# cp2102n-uart-usb.net
KiCad netlist of a schematic drawn in EAGLE
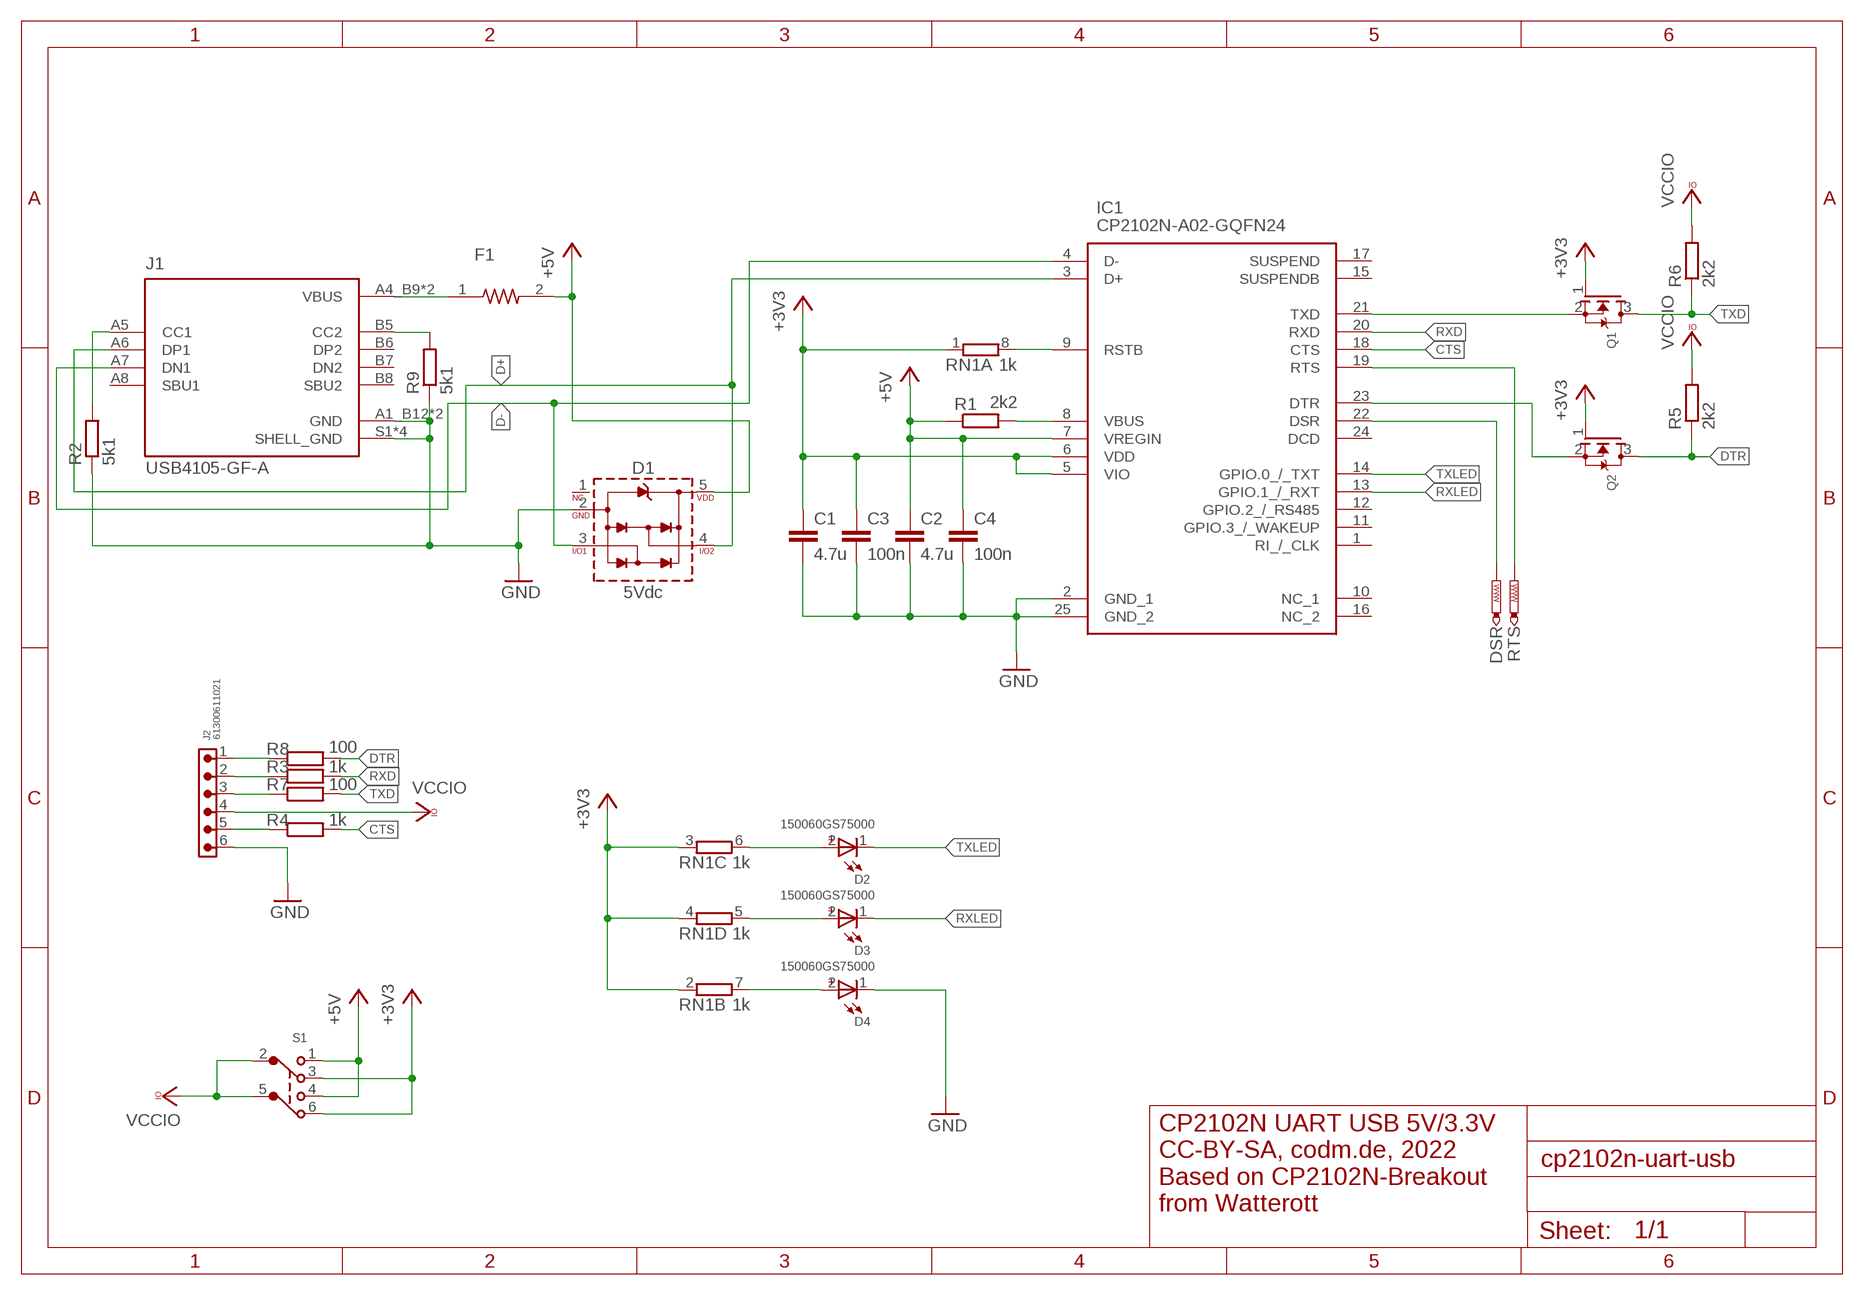
[diagram p0: schematic, sheet 1]

(export (version "E")
  (design (tool "Eeschema 10.0.6"))
  (components
    (comp (ref "C1")
      (value "4.7u")
      (footprint "eagle-import:C0603K")
      (libsource (lib "eagle-import") (part "C-EUC0603K"))
    )
    (comp (ref "C2")
      (value "4.7u")
      (footprint "eagle-import:C0603K")
      (libsource (lib "eagle-import") (part "C-EUC0603K"))
    )
    (comp (ref "C3")
      (value "100n")
      (footprint "eagle-import:C0603K")
      (libsource (lib "eagle-import") (part "C-EUC0603K"))
    )
    (comp (ref "C4")
      (value "100n")
      (footprint "eagle-import:C0603K")
      (libsource (lib "eagle-import") (part "C-EUC0603K"))
    )
    (comp (ref "D1")
      (value "5Vdc")
      (footprint "eagle-import:WE-TVS_SOT23-5L")
      (libsource (lib "eagle-import") (part "WE-TVS-HS_SOT23-5L_824011"))
    )
    (comp (ref "D2")
      (value "150060GS75000")
      (footprint "eagle-import:WL-SMCW_0603")
      (libsource (lib "eagle-import") (part "WL-SMCW_0603_150060GS75000"))
    )
    (comp (ref "D3")
      (value "150060GS75000")
      (footprint "eagle-import:WL-SMCW_0603")
      (libsource (lib "eagle-import") (part "WL-SMCW_0603_150060GS75000"))
    )
    (comp (ref "D4")
      (value "150060GS75000")
      (footprint "eagle-import:WL-SMCW_0603")
      (libsource (lib "eagle-import") (part "WL-SMCW_0603_150060GS75000"))
    )
    (comp (ref "DSR")
      (value "PTR1B2,54")
      (footprint "eagle-import:B2,54")
      (libsource (lib "eagle-import") (part "PTR1B2,54"))
    )
    (comp (ref "F1")
      (value "PICOSMDC050S-2")
      (footprint "eagle-import:RESC2012X65N")
      (fields (field (name "MF") "Littelfuse Inc."))
      (libsource (lib "eagle-import") (part "PICOSMDC050S-2"))
    )
    (comp (ref "IC1")
      (value "CP2102N-A02-GQFN24")
      (footprint "eagle-import:QFN50P400X400X80-25N")
      (fields (field (name "MF") "Silicon Labs"))
      (libsource (lib "eagle-import") (part "CP2102N-A02-GQFN24"))
    )
    (comp (ref "J1")
      (value "USB4105-GF-A")
      (footprint "eagle-import:GCT_USB4105-GF-A")
      (fields (field (name "MF") "GCT"))
      (libsource (lib "eagle-import") (part "USB4105-GF-A"))
    )
    (comp (ref "J2")
      (value "61300611021")
      (footprint "eagle-import:61300611021")
      (libsource (lib "eagle-import") (part "6130XX11021_61300611021"))
    )
    (comp (ref "Q1")
      (value "MOSFET-NREFLOW")
      (footprint "eagle-import:SOT23")
      (libsource (lib "eagle-import") (part "MOSFET-NREFLOW"))
    )
    (comp (ref "Q2")
      (value "MOSFET-NREFLOW")
      (footprint "eagle-import:SOT23")
      (libsource (lib "eagle-import") (part "MOSFET-NREFLOW"))
    )
    (comp (ref "R1")
      (value "2k2")
      (footprint "eagle-import:R0603RF")
      (libsource (lib "eagle-import") (part "R-EU_R0603RF"))
    )
    (comp (ref "R2")
      (value "5k1")
      (footprint "eagle-import:R0603RF")
      (libsource (lib "eagle-import") (part "R-EU_R0603RF"))
    )
    (comp (ref "R3")
      (value "1k")
      (footprint "eagle-import:R0603RF")
      (libsource (lib "eagle-import") (part "R-EU_R0603RF"))
    )
    (comp (ref "R4")
      (value "1k")
      (footprint "eagle-import:R0603RF")
      (libsource (lib "eagle-import") (part "R-EU_R0603RF"))
    )
    (comp (ref "R5")
      (value "2k2")
      (footprint "eagle-import:R0603RF")
      (libsource (lib "eagle-import") (part "R-EU_R0603RF"))
    )
    (comp (ref "R6")
      (value "2k2")
      (footprint "eagle-import:R0603RF")
      (libsource (lib "eagle-import") (part "R-EU_R0603RF"))
    )
    (comp (ref "R7")
      (value "100")
      (footprint "eagle-import:R0603RF")
      (libsource (lib "eagle-import") (part "R-EU_R0603RF"))
    )
    (comp (ref "R8")
      (value "100")
      (footprint "eagle-import:R0603RF")
      (libsource (lib "eagle-import") (part "R-EU_R0603RF"))
    )
    (comp (ref "R9")
      (value "5k1")
      (footprint "eagle-import:R0603RF")
      (libsource (lib "eagle-import") (part "R-EU_R0603RF"))
    )
    (comp (ref "RN1")
      (value "1k")
      (footprint "eagle-import:EXB38V")
      (libsource (lib "eagle-import") (part "4R-NEXB38V"))
    )
    (comp (ref "RTS")
      (value "PTR1B2,54")
      (footprint "eagle-import:B2,54")
      (libsource (lib "eagle-import") (part "PTR1B2,54"))
    )
    (comp (ref "S1")
      (value "452403012014")
      (footprint "eagle-import:452403012014")
      (libsource (lib "eagle-import") (part "452403012014"))
    )
  )
  (nets
    (net (code "1") (name "+3V3") (class "Default")
      (node (ref "C1") (pin "1") (pinfunction "1_1") (pintype "passive"))
      (node (ref "C3") (pin "1") (pinfunction "1_1") (pintype "passive"))
      (node (ref "IC1") (pin "5") (pinfunction "VIO_5") (pintype "power_in"))
      (node (ref "IC1") (pin "6") (pinfunction "VDD_6") (pintype "power_in"))
      (node (ref "Q1") (pin "1") (pinfunction "G_1") (pintype "bidirectional"))
      (node (ref "Q2") (pin "1") (pinfunction "G_1") (pintype "bidirectional"))
      (node (ref "RN1") (pin "1") (pinfunction "1_1") (pintype "passive"))
      (node (ref "RN1") (pin "2") (pinfunction "1_2") (pintype "passive"))
      (node (ref "RN1") (pin "3") (pinfunction "1_3") (pintype "passive"))
      (node (ref "RN1") (pin "4") (pinfunction "1_4") (pintype "passive"))
      (node (ref "S1") (pin "3") (pinfunction "3_3") (pintype "passive"))
      (node (ref "S1") (pin "6") (pinfunction "6_6") (pintype "passive"))
    )
    (net (code "2") (name "+5V") (class "Default")
      (node (ref "C2") (pin "1") (pinfunction "1_1") (pintype "passive"))
      (node (ref "C4") (pin "1") (pinfunction "1_1") (pintype "passive"))
      (node (ref "D1") (pin "5") (pinfunction "VDD_5") (pintype "passive"))
      (node (ref "F1") (pin "2") (pinfunction "2_2") (pintype "passive"))
      (node (ref "IC1") (pin "7") (pinfunction "VREGIN_7") (pintype "power_in"))
      (node (ref "R1") (pin "1") (pinfunction "1_1") (pintype "passive"))
      (node (ref "S1") (pin "1") (pinfunction "1_1") (pintype "passive"))
      (node (ref "S1") (pin "4") (pinfunction "4_4") (pintype "passive"))
    )
    (net (code "3") (name "CTS") (class "Default")
      (node (ref "IC1") (pin "18") (pinfunction "CTS_18") (pintype "bidirectional"))
      (node (ref "R4") (pin "2") (pinfunction "2_2") (pintype "passive"))
    )
    (net (code "4") (name "D+") (class "Default")
      (node (ref "D1") (pin "4") (pinfunction "I/O2_4") (pintype "passive"))
      (node (ref "IC1") (pin "3") (pinfunction "D+_3") (pintype "bidirectional"))
      (node (ref "J1") (pin "A6") (pinfunction "DP1_A6") (pintype "bidirectional"))
    )
    (net (code "5") (name "D-") (class "Default")
      (node (ref "D1") (pin "3") (pinfunction "I/O1_3") (pintype "passive"))
      (node (ref "IC1") (pin "4") (pinfunction "D-_4") (pintype "bidirectional"))
      (node (ref "J1") (pin "A7") (pinfunction "DN1_A7") (pintype "bidirectional"))
    )
    (net (code "6") (name "DTR") (class "Default")
      (node (ref "Q2") (pin "3") (pinfunction "D_3") (pintype "bidirectional"))
      (node (ref "R5") (pin "1") (pinfunction "1_1") (pintype "passive"))
      (node (ref "R8") (pin "2") (pinfunction "2_2") (pintype "passive"))
    )
    (net (code "7") (name "GND") (class "Default")
      (node (ref "C1") (pin "2") (pinfunction "2_2") (pintype "passive"))
      (node (ref "C2") (pin "2") (pinfunction "2_2") (pintype "passive"))
      (node (ref "C3") (pin "2") (pinfunction "2_2") (pintype "passive"))
      (node (ref "C4") (pin "2") (pinfunction "2_2") (pintype "passive"))
      (node (ref "D1") (pin "2") (pinfunction "GND_2") (pintype "passive"))
      (node (ref "D4") (pin "1") (pinfunction "-_1") (pintype "passive"))
      (node (ref "IC1") (pin "2") (pinfunction "GND_1_2") (pintype "power_in"))
      (node (ref "IC1") (pin "25") (pinfunction "GND_2_25") (pintype "power_in"))
      (node (ref "J1") (pin "A1_B12") (pinfunction "GND_A1_B12") (pintype "power_in"))
      (node (ref "J1") (pin "B1_A12") (pinfunction "GND_B1_A12") (pintype "power_in"))
      (node (ref "J1") (pin "S1") (pinfunction "SHELL_GND_S1") (pintype "power_in"))
      (node (ref "J1") (pin "S2") (pinfunction "SHELL_GND_S2") (pintype "power_in"))
      (node (ref "J1") (pin "S3") (pinfunction "SHELL_GND_S3") (pintype "power_in"))
      (node (ref "J1") (pin "S4") (pinfunction "SHELL_GND_S4") (pintype "power_in"))
      (node (ref "J2") (pin "6") (pinfunction "6_6") (pintype "passive"))
      (node (ref "R2") (pin "1") (pinfunction "1_1") (pintype "passive"))
      (node (ref "R9") (pin "1") (pinfunction "1_1") (pintype "passive"))
    )
    (net (code "8") (name "Net-(D2-+)") (class "Default")
      (node (ref "D2") (pin "2") (pinfunction "+_2") (pintype "passive"))
      (node (ref "RN1") (pin "6") (pinfunction "2_6") (pintype "passive"))
    )
    (net (code "9") (name "Net-(D3-+)") (class "Default")
      (node (ref "D3") (pin "2") (pinfunction "+_2") (pintype "passive"))
      (node (ref "RN1") (pin "5") (pinfunction "2_5") (pintype "passive"))
    )
    (net (code "10") (name "Net-(D4-+)") (class "Default")
      (node (ref "D4") (pin "2") (pinfunction "+_2") (pintype "passive"))
      (node (ref "RN1") (pin "7") (pinfunction "2_7") (pintype "passive"))
    )
    (net (code "11") (name "Net-(F1-Pad1)") (class "Default")
      (node (ref "F1") (pin "1") (pinfunction "1_1") (pintype "passive"))
      (node (ref "J1") (pin "A4_B9") (pinfunction "VBUS_A4_B9") (pintype "power_in"))
      (node (ref "J1") (pin "B4_A9") (pinfunction "VBUS_B4_A9") (pintype "power_in"))
    )
    (net (code "12") (name "Net-(IC1-DSR)") (class "Default")
      (node (ref "DSR") (pin "TP") (pinfunction "TP_TP") (pintype "input"))
      (node (ref "IC1") (pin "22") (pinfunction "DSR_22") (pintype "bidirectional"))
    )
    (net (code "13") (name "Net-(IC1-DTR)") (class "Default")
      (node (ref "IC1") (pin "23") (pinfunction "DTR_23") (pintype "bidirectional"))
      (node (ref "Q2") (pin "2") (pinfunction "S_2") (pintype "bidirectional"))
    )
    (net (code "14") (name "Net-(IC1-RSTB)") (class "Default")
      (node (ref "IC1") (pin "9") (pinfunction "RSTB_9") (pintype "bidirectional"))
      (node (ref "RN1") (pin "8") (pinfunction "2_8") (pintype "passive"))
    )
    (net (code "15") (name "Net-(IC1-RTS)") (class "Default")
      (node (ref "IC1") (pin "19") (pinfunction "RTS_19") (pintype "output"))
      (node (ref "RTS") (pin "TP") (pinfunction "TP_TP") (pintype "input"))
    )
    (net (code "16") (name "Net-(IC1-TXD)") (class "Default")
      (node (ref "IC1") (pin "21") (pinfunction "TXD_21") (pintype "output"))
      (node (ref "Q1") (pin "2") (pinfunction "S_2") (pintype "bidirectional"))
    )
    (net (code "17") (name "Net-(IC1-VBUS)") (class "Default")
      (node (ref "IC1") (pin "8") (pinfunction "VBUS_8") (pintype "power_in"))
      (node (ref "R1") (pin "2") (pinfunction "2_2") (pintype "passive"))
    )
    (net (code "18") (name "Net-(J1-CC1)") (class "Default")
      (node (ref "J1") (pin "A5") (pinfunction "CC1_A5") (pintype "bidirectional"))
      (node (ref "R2") (pin "2") (pinfunction "2_2") (pintype "passive"))
    )
    (net (code "19") (name "Net-(J1-CC2)") (class "Default")
      (node (ref "J1") (pin "B5") (pinfunction "CC2_B5") (pintype "bidirectional"))
      (node (ref "R9") (pin "2") (pinfunction "2_2") (pintype "passive"))
    )
    (net (code "20") (name "Net-(J2-Pad1)") (class "Default")
      (node (ref "J2") (pin "1") (pinfunction "1_1") (pintype "passive"))
      (node (ref "R8") (pin "1") (pinfunction "1_1") (pintype "passive"))
    )
    (net (code "21") (name "Net-(J2-Pad2)") (class "Default")
      (node (ref "J2") (pin "2") (pinfunction "2_2") (pintype "passive"))
      (node (ref "R3") (pin "1") (pinfunction "1_1") (pintype "passive"))
    )
    (net (code "22") (name "Net-(J2-Pad3)") (class "Default")
      (node (ref "J2") (pin "3") (pinfunction "3_3") (pintype "passive"))
      (node (ref "R7") (pin "1") (pinfunction "1_1") (pintype "passive"))
    )
    (net (code "23") (name "Net-(J2-Pad5)") (class "Default")
      (node (ref "J2") (pin "5") (pinfunction "5_5") (pintype "passive"))
      (node (ref "R4") (pin "1") (pinfunction "1_1") (pintype "passive"))
    )
    (net (code "24") (name "RXD") (class "Default")
      (node (ref "IC1") (pin "20") (pinfunction "RXD_20") (pintype "input"))
      (node (ref "R3") (pin "2") (pinfunction "2_2") (pintype "passive"))
    )
    (net (code "25") (name "RXLED") (class "Default")
      (node (ref "D3") (pin "1") (pinfunction "-_1") (pintype "passive"))
      (node (ref "IC1") (pin "13") (pinfunction "GPIO.1_/_RXT_13") (pintype "bidirectional"))
    )
    (net (code "26") (name "TXD") (class "Default")
      (node (ref "Q1") (pin "3") (pinfunction "D_3") (pintype "bidirectional"))
      (node (ref "R6") (pin "1") (pinfunction "1_1") (pintype "passive"))
      (node (ref "R7") (pin "2") (pinfunction "2_2") (pintype "passive"))
    )
    (net (code "27") (name "TXLED") (class "Default")
      (node (ref "D2") (pin "1") (pinfunction "-_1") (pintype "passive"))
      (node (ref "IC1") (pin "14") (pinfunction "GPIO.0_/_TXT_14") (pintype "bidirectional"))
    )
    (net (code "28") (name "VCCIO") (class "Default")
      (node (ref "J2") (pin "4") (pinfunction "4_4") (pintype "passive"))
      (node (ref "R5") (pin "2") (pinfunction "2_2") (pintype "passive"))
      (node (ref "R6") (pin "2") (pinfunction "2_2") (pintype "passive"))
      (node (ref "S1") (pin "2") (pinfunction "2_2") (pintype "passive"))
      (node (ref "S1") (pin "5") (pinfunction "5_5") (pintype "passive"))
    )
    (net (code "29") (name "unconnected-(D1-NC-Pad1)") (class "Default")
      (node (ref "D1") (pin "1") (pinfunction "NC_1") (pintype "passive"))
    )
    (net (code "30") (name "unconnected-(IC1-DCD-Pad24)") (class "Default")
      (node (ref "IC1") (pin "24") (pinfunction "DCD_24") (pintype "bidirectional"))
    )
    (net (code "31") (name "unconnected-(IC1-GPIO.2_{slash}_RS485-Pad12)") (class "Default")
      (node (ref "IC1") (pin "12") (pinfunction "GPIO.2_/_RS485_12") (pintype "bidirectional"))
    )
    (net (code "32") (name "unconnected-(IC1-GPIO.3_{slash}_WAKEUP-Pad11)") (class "Default")
      (node (ref "IC1") (pin "11") (pinfunction "GPIO.3_/_WAKEUP_11") (pintype "bidirectional"))
    )
    (net (code "33") (name "unconnected-(IC1-NC_1-Pad10)") (class "Default")
      (node (ref "IC1") (pin "10") (pinfunction "NC_1_10") (pintype "no_connect"))
    )
    (net (code "34") (name "unconnected-(IC1-NC_2-Pad16)") (class "Default")
      (node (ref "IC1") (pin "16") (pinfunction "NC_2_16") (pintype "no_connect"))
    )
    (net (code "35") (name "unconnected-(IC1-RI_{slash}_CLK-Pad1)") (class "Default")
      (node (ref "IC1") (pin "1") (pinfunction "RI_/_CLK_1") (pintype "bidirectional"))
    )
    (net (code "36") (name "unconnected-(IC1-SUSPEND-Pad17)") (class "Default")
      (node (ref "IC1") (pin "17") (pinfunction "SUSPEND_17") (pintype "output"))
    )
    (net (code "37") (name "unconnected-(IC1-SUSPENDB-Pad15)") (class "Default")
      (node (ref "IC1") (pin "15") (pinfunction "SUSPENDB_15") (pintype "output"))
    )
    (net (code "38") (name "unconnected-(J1-DN2-PadB7)") (class "Default")
      (node (ref "J1") (pin "B7") (pinfunction "DN2_B7") (pintype "bidirectional"))
    )
    (net (code "39") (name "unconnected-(J1-DP2-PadB6)") (class "Default")
      (node (ref "J1") (pin "B6") (pinfunction "DP2_B6") (pintype "bidirectional"))
    )
    (net (code "40") (name "unconnected-(J1-SBU1-PadA8)") (class "Default")
      (node (ref "J1") (pin "A8") (pinfunction "SBU1_A8") (pintype "bidirectional"))
    )
    (net (code "41") (name "unconnected-(J1-SBU2-PadB8)") (class "Default")
      (node (ref "J1") (pin "B8") (pinfunction "SBU2_B8") (pintype "bidirectional"))
    )
  )
)
